# 74LVC74AD.net
KiCad netlist of a schematic drawn in Altium Designer
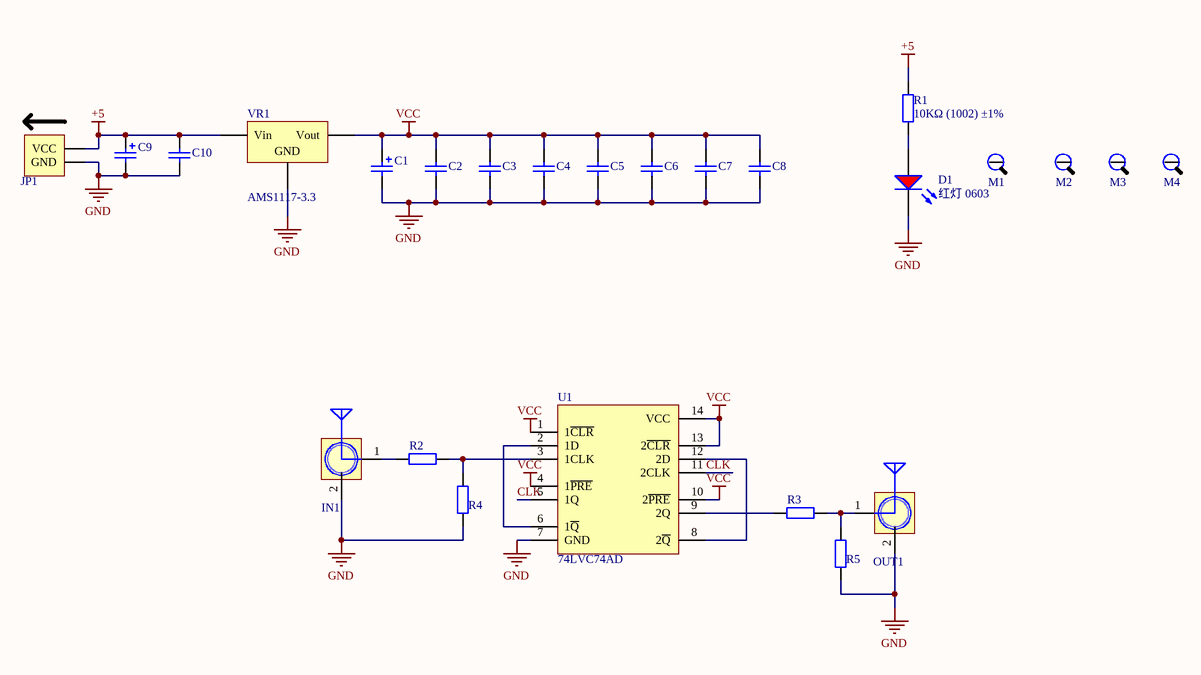
[diagram p0: 74LVC74AD.SchDoc]

(export (version "E")
  (design (tool "Eeschema 10.0.6"))
  (components
    (comp (ref "C1")
      (value "10uF (106) ±10% 16V")
      (footprint "CASE-A_3216")
      (description "钽电容")
      (libsource (lib "JLC") (part "3216 10uF (106) 10% 16V"))
    )
    (comp (ref "C2")
      (value "100nF (104) 10% 50V")
      (footprint "0603_C")
      (description "贴片电容")
      (libsource (lib "JLC") (part "0603 100nF (104) 10% 50V"))
    )
    (comp (ref "C3")
      (value "100nF (104) 10% 50V")
      (footprint "0603_C")
      (description "贴片电容")
      (libsource (lib "JLC") (part "0603 100nF (104) 10% 50V"))
    )
    (comp (ref "C4")
      (value "100nF (104) 10% 50V")
      (footprint "0603_C")
      (description "贴片电容")
      (libsource (lib "JLC") (part "0603 100nF (104) 10% 50V"))
    )
    (comp (ref "C5")
      (value "100nF (104) 10% 50V")
      (footprint "0603_C")
      (description "贴片电容")
      (libsource (lib "JLC") (part "0603 100nF (104) 10% 50V"))
    )
    (comp (ref "C6")
      (value "100nF (104) 10% 50V")
      (footprint "0603_C")
      (description "贴片电容")
      (libsource (lib "JLC") (part "0603 100nF (104) 10% 50V"))
    )
    (comp (ref "C7")
      (value "100nF (104) 10% 50V")
      (footprint "0603_C")
      (description "贴片电容")
      (libsource (lib "JLC") (part "0603 100nF (104) 10% 50V"))
    )
    (comp (ref "C8")
      (value "100nF (104) 10% 50V")
      (footprint "0603_C")
      (description "贴片电容")
      (libsource (lib "JLC") (part "0603 100nF (104) 10% 50V"))
    )
    (comp (ref "C9")
      (value "10uF (106) ±10% 16V")
      (footprint "CASE-A_3216")
      (description "钽电容")
      (libsource (lib "JLC") (part "3216 10uF (106) 10% 16V"))
    )
    (comp (ref "C10")
      (value "100nF (104) 10% 50V")
      (footprint "0603_C")
      (description "贴片电容")
      (libsource (lib "JLC") (part "0603 100nF (104) 10% 50V"))
    )
    (comp (ref "D1")
      (value "红灯 0603")
      (footprint "0603_LED_S1")
      (description "发光二极管")
      (libsource (lib "JLC") (part "0603 红灯"))
    )
    (comp (ref "IN1")
      (value "SMA WIFI 天线接口")
      (footprint "SMA")
      (description "SMA-2.4G射频天线接口")
      (fields (field (name "版权归属") "源创客"))
      (libsource (lib "") (part "PORT_SMA_1"))
    )
    (comp (ref "JP1")
      (value "HDR-1X2")
      (footprint "Power_IN_3.81-2P")
      (description "2P接插件,模块单电源供电口")
      (fields (field (name "版权归属") "源创客"))
      (libsource (lib "Cooperation") (part "PORT_Power_IN2"))
    )
    (comp (ref "M1")
      (value "M3")
      (footprint "M3x10_L")
      (description "螺丝")
      (libsource (lib "Cooperation") (part "ELSE_M3_screw"))
    )
    (comp (ref "M2")
      (value "M3")
      (footprint "M3x10_L")
      (description "螺丝")
      (libsource (lib "Cooperation") (part "ELSE_M3_screw"))
    )
    (comp (ref "M3")
      (value "M3")
      (footprint "M3x10_L")
      (description "螺丝")
      (libsource (lib "Cooperation") (part "ELSE_M3_screw"))
    )
    (comp (ref "M4")
      (value "M3")
      (footprint "M3x10_L")
      (description "螺丝")
      (libsource (lib "Cooperation") (part "ELSE_M3_screw"))
    )
    (comp (ref "OUT1")
      (value "SMA WIFI 天线接口")
      (footprint "SMA")
      (description "SMA-2.4G射频天线接口")
      (fields (field (name "版权归属") "源创客"))
      (libsource (lib "Cooperation") (part "PORT_SMA"))
    )
    (comp (ref "R1")
      (value "10KΩ (1002) ±1%")
      (footprint "0603_R")
      (description "贴片电阻")
      (libsource (lib "JLC") (part "0603 10KΩ (1002) 1%"))
    )
    (comp (ref "R2")
      (value "10KΩ (1002) ±1%")
      (footprint "0603_R")
      (description "贴片电阻")
      (libsource (lib "") (part "0603 10KΩ (1002) 1%_1"))
    )
    (comp (ref "R3")
      (value "10KΩ (1002) ±1%")
      (footprint "0603_R")
      (description "贴片电阻")
      (libsource (lib "") (part "0603 10KΩ (1002) 1%_1"))
    )
    (comp (ref "R4")
      (value "10KΩ (1002) ±1%")
      (footprint "0603_R")
      (description "贴片电阻")
      (libsource (lib "") (part "0603 10KΩ (1002) 1%_2"))
    )
    (comp (ref "R5")
      (value "10KΩ (1002) ±1%")
      (footprint "0603_R")
      (description "贴片电阻")
      (libsource (lib "") (part "0603 10KΩ (1002) 1%_2"))
    )
    (comp (ref "U1")
      (value "74LVC74AD")
      (footprint "SOIC_14")
      (libsource (lib "Cooperation") (part "74LVC74AD"))
    )
    (comp (ref "VR1")
      (value "AMS1117-3.3")
      (footprint "SOT-223")
      (description "低压差线性稳压(LDO)")
      (libsource (lib "JLC") (part "SOT-223 AMS1117-3.3"))
    )
  )
  (nets
    (net (code "1") (name "+5") (class "Default")
      (node (ref "C10") (pin "2") (pinfunction "2_2") (pintype "passive"))
      (node (ref "C9") (pin "1") (pinfunction "1_1") (pintype "passive"))
      (node (ref "JP1") (pin "1") (pinfunction "VCC_1") (pintype "passive"))
      (node (ref "R1") (pin "2") (pinfunction "2_2") (pintype "passive"))
      (node (ref "VR1") (pin "3") (pinfunction "Vin_3") (pintype "passive"))
    )
    (net (code "2") (name "/CLK") (class "Default")
      (node (ref "U1") (pin "11") (pinfunction "2CLK_11") (pintype "passive"))
      (node (ref "U1") (pin "5") (pinfunction "1Q_5") (pintype "passive"))
    )
    (net (code "3") (name "GND") (class "Default")
      (node (ref "C1") (pin "2") (pinfunction "2_2") (pintype "passive"))
      (node (ref "C10") (pin "1") (pinfunction "1_1") (pintype "passive"))
      (node (ref "C2") (pin "1") (pinfunction "1_1") (pintype "passive"))
      (node (ref "C3") (pin "1") (pinfunction "1_1") (pintype "passive"))
      (node (ref "C4") (pin "1") (pinfunction "1_1") (pintype "passive"))
      (node (ref "C5") (pin "1") (pinfunction "1_1") (pintype "passive"))
      (node (ref "C6") (pin "1") (pinfunction "1_1") (pintype "passive"))
      (node (ref "C7") (pin "1") (pinfunction "1_1") (pintype "passive"))
      (node (ref "C8") (pin "1") (pinfunction "1_1") (pintype "passive"))
      (node (ref "C9") (pin "2") (pinfunction "2_2") (pintype "passive"))
      (node (ref "D1") (pin "K") (pinfunction "K_K") (pintype "passive"))
      (node (ref "IN1") (pin "2") (pinfunction "2_2") (pintype "passive"))
      (node (ref "JP1") (pin "2") (pinfunction "GND_2") (pintype "passive"))
      (node (ref "OUT1") (pin "2") (pinfunction "2_2") (pintype "passive"))
      (node (ref "R4") (pin "2") (pinfunction "2_2") (pintype "passive"))
      (node (ref "R5") (pin "2") (pinfunction "2_2") (pintype "passive"))
      (node (ref "U1") (pin "7") (pinfunction "GND_7") (pintype "passive"))
      (node (ref "VR1") (pin "1") (pinfunction "GND_1") (pintype "passive"))
    )
    (net (code "4") (name "Net-(D1-PadA)") (class "Default")
      (node (ref "D1") (pin "A") (pinfunction "A_A") (pintype "passive"))
      (node (ref "R1") (pin "1") (pinfunction "1_1") (pintype "passive"))
    )
    (net (code "5") (name "Net-(IN1-SINGLE)") (class "Default")
      (node (ref "IN1") (pin "1") (pinfunction "SINGLE_1") (pintype "passive"))
      (node (ref "R2") (pin "2") (pinfunction "2_2") (pintype "passive"))
    )
    (net (code "6") (name "Net-(OUT1-SINGLE)") (class "Default")
      (node (ref "OUT1") (pin "1") (pinfunction "SINGLE_1") (pintype "passive"))
      (node (ref "R3") (pin "1") (pinfunction "1_1") (pintype "passive"))
      (node (ref "R5") (pin "1") (pinfunction "1_1") (pintype "passive"))
    )
    (net (code "7") (name "Net-(U1-1CLK)") (class "Default")
      (node (ref "R2") (pin "1") (pinfunction "1_1") (pintype "passive"))
      (node (ref "R4") (pin "1") (pinfunction "1_1") (pintype "passive"))
      (node (ref "U1") (pin "3") (pinfunction "1CLK_3") (pintype "passive"))
    )
    (net (code "8") (name "Net-(U1-1D)") (class "Default")
      (node (ref "U1") (pin "2") (pinfunction "1D_2") (pintype "passive"))
      (node (ref "U1") (pin "6") (pinfunction "1~{Q}_6") (pintype "passive"))
    )
    (net (code "9") (name "Net-(U1-2D)") (class "Default")
      (node (ref "U1") (pin "12") (pinfunction "2D_12") (pintype "passive"))
      (node (ref "U1") (pin "8") (pinfunction "2~{Q}_8") (pintype "passive"))
    )
    (net (code "10") (name "Net-(U1-2Q)") (class "Default")
      (node (ref "R3") (pin "2") (pinfunction "2_2") (pintype "passive"))
      (node (ref "U1") (pin "9") (pinfunction "2Q_9") (pintype "passive"))
    )
    (net (code "11") (name "VCC") (class "Default")
      (node (ref "C1") (pin "1") (pinfunction "1_1") (pintype "passive"))
      (node (ref "C2") (pin "2") (pinfunction "2_2") (pintype "passive"))
      (node (ref "C3") (pin "2") (pinfunction "2_2") (pintype "passive"))
      (node (ref "C4") (pin "2") (pinfunction "2_2") (pintype "passive"))
      (node (ref "C5") (pin "2") (pinfunction "2_2") (pintype "passive"))
      (node (ref "C6") (pin "2") (pinfunction "2_2") (pintype "passive"))
      (node (ref "C7") (pin "2") (pinfunction "2_2") (pintype "passive"))
      (node (ref "C8") (pin "2") (pinfunction "2_2") (pintype "passive"))
      (node (ref "U1") (pin "1") (pinfunction "1~{CLR}_1") (pintype "passive"))
      (node (ref "U1") (pin "10") (pinfunction "2~{PRE}_10") (pintype "passive"))
      (node (ref "U1") (pin "13") (pinfunction "2~{CLR}_13") (pintype "passive"))
      (node (ref "U1") (pin "14") (pinfunction "VCC_14") (pintype "passive"))
      (node (ref "U1") (pin "4") (pinfunction "1~{PRE}_4") (pintype "passive"))
      (node (ref "VR1") (pin "2") (pinfunction "Vout_2") (pintype "passive"))
    )
    (net (code "12") (name "unconnected-(M1-Pad1)") (class "Default")
      (node (ref "M1") (pin "1") (pinfunction "1_1") (pintype "passive"))
    )
    (net (code "13") (name "unconnected-(M2-Pad1)") (class "Default")
      (node (ref "M2") (pin "1") (pinfunction "1_1") (pintype "passive"))
    )
    (net (code "14") (name "unconnected-(M3-Pad1)") (class "Default")
      (node (ref "M3") (pin "1") (pinfunction "1_1") (pintype "passive"))
    )
    (net (code "15") (name "unconnected-(M4-Pad1)") (class "Default")
      (node (ref "M4") (pin "1") (pinfunction "1_1") (pintype "passive"))
    )
  )
)
